# CardV1-ASCII.net
KiCad netlist of a schematic drawn in Altium Designer
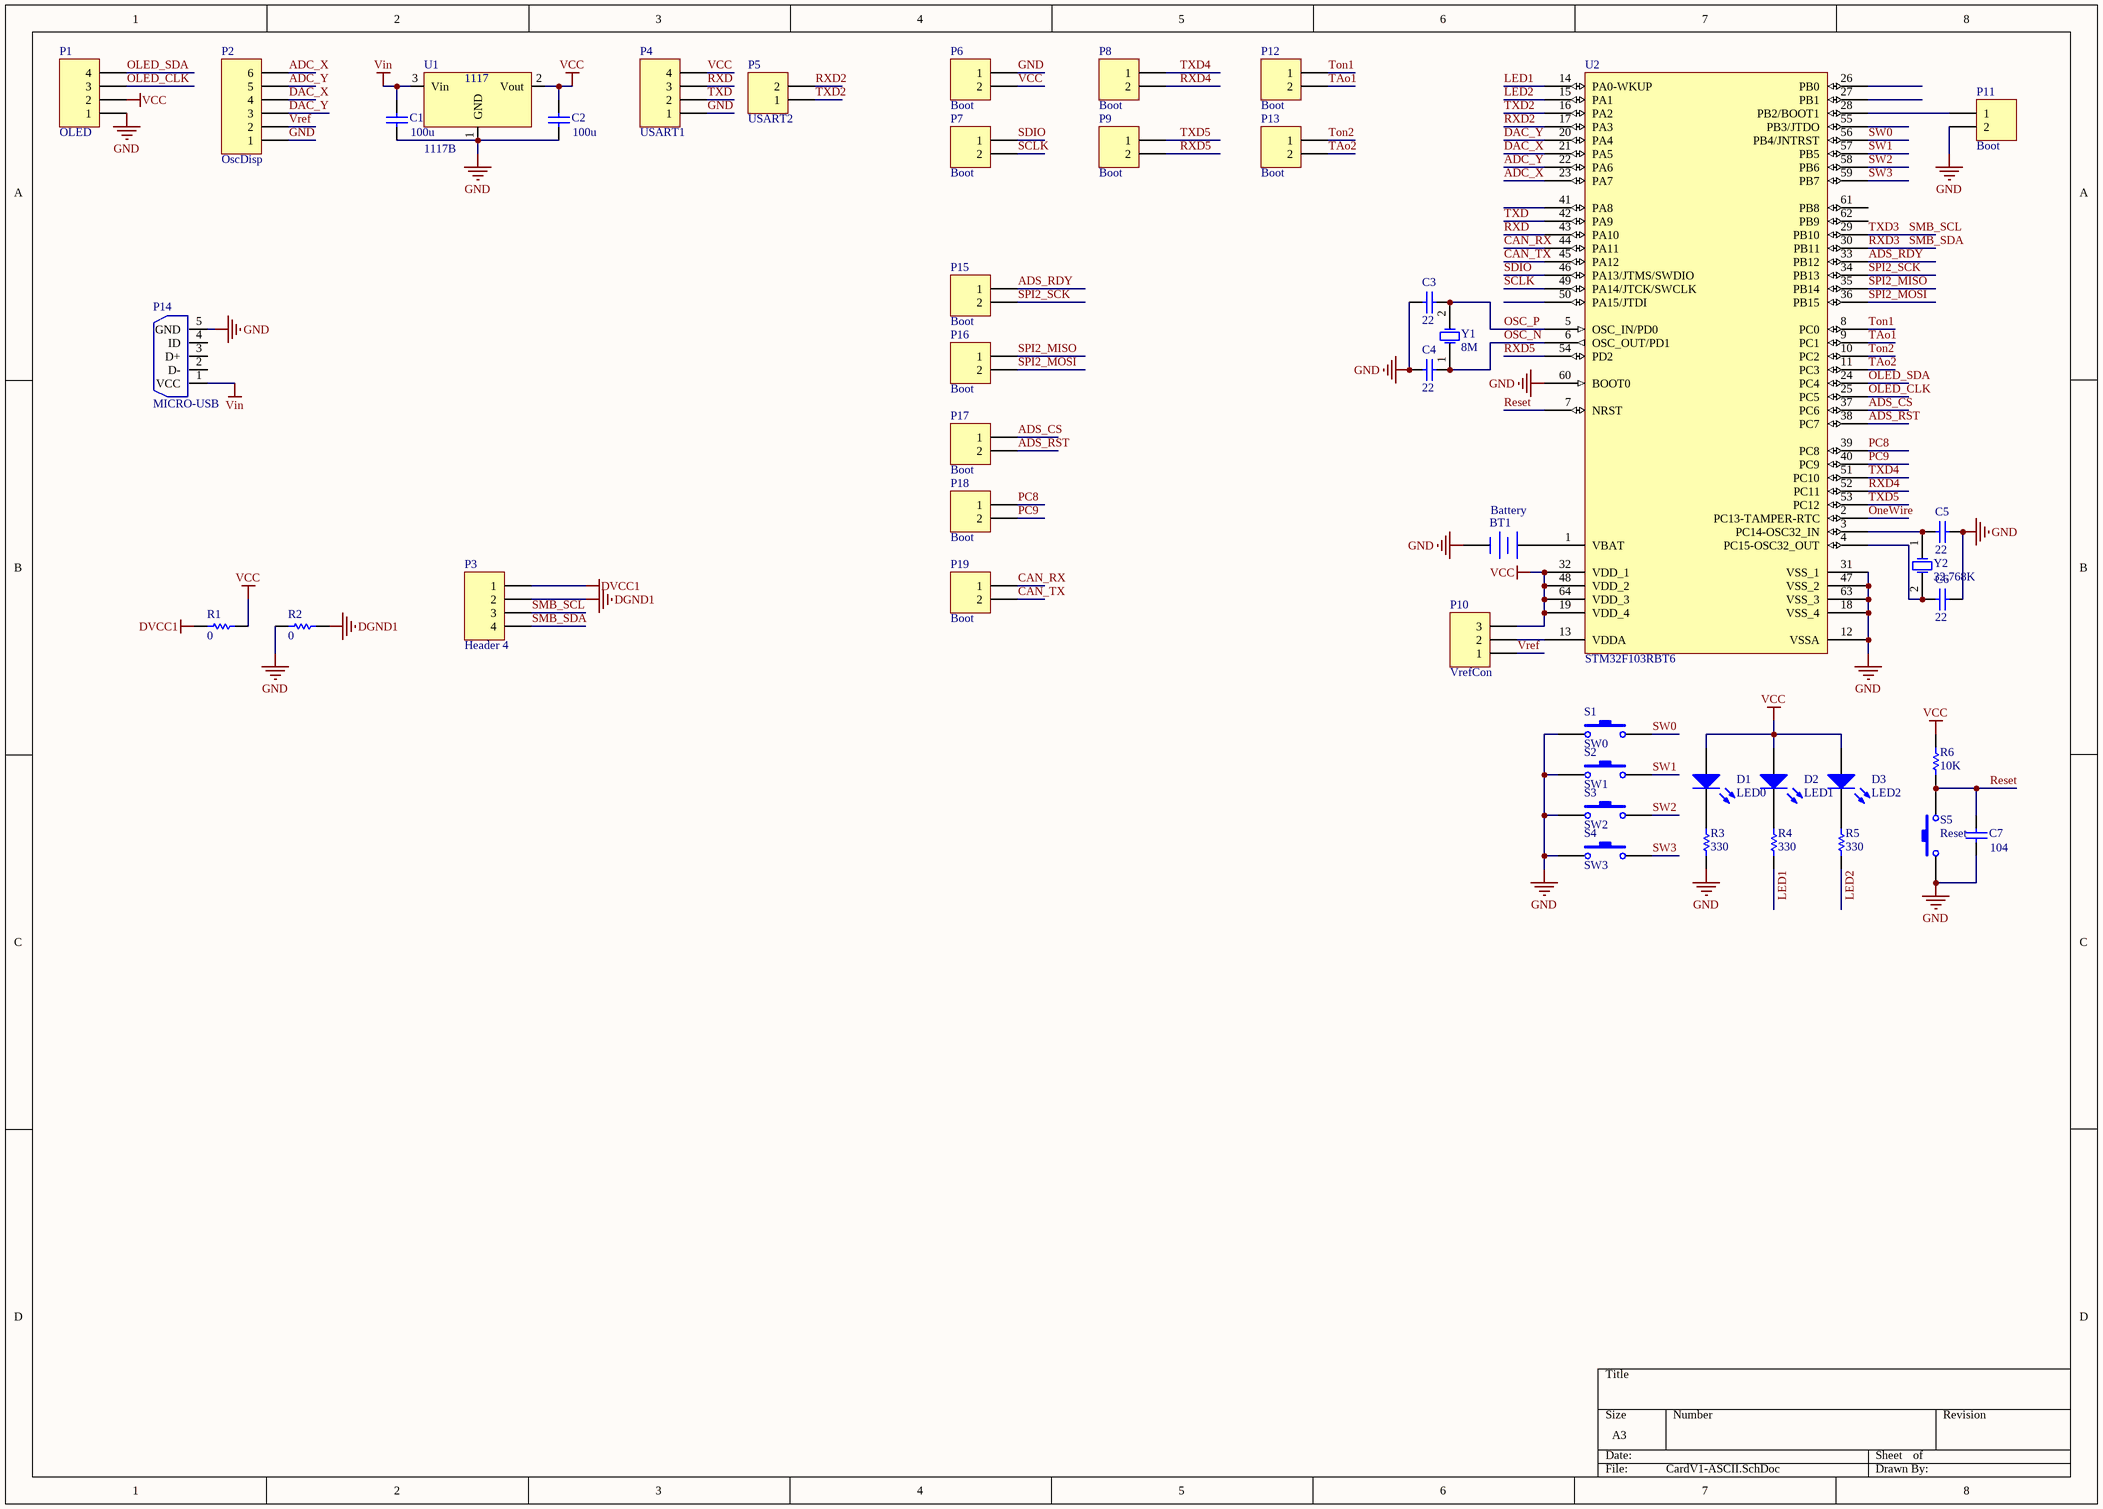
[diagram p0: CardV1-ASCII.SchDoc]

(export (version "E")
  (design (tool "Eeschema 10.0.6"))
  (components
    (comp (ref "BT1")
      (value "Battery")
      (footprint "Battery-OneSide")
      (description "Multicell Battery")
      (fields (field (name "PUBLISHER") "Altium Limited"))
      (libsource (lib "Miscellaneous Devices") (part "Battery"))
    )
    (comp (ref "C1")
      (value "100u")
      (footprint "1608[0603]")
      (description "Capacitor")
      (fields (field (name "PUBLISHER") "Altium Limited"))
      (libsource (lib "Miscellaneous Devices") (part "Cap"))
    )
    (comp (ref "C2")
      (value "100u")
      (footprint "1608[0603]")
      (description "Capacitor")
      (fields (field (name "PUBLISHER") "Altium Limited"))
      (libsource (lib "Miscellaneous Devices") (part "Cap"))
    )
    (comp (ref "C3")
      (value "22")
      (footprint "1608[0603]")
      (description "Capacitor")
      (fields (field (name "PUBLISHER") "Altium Limited"))
      (libsource (lib "Miscellaneous Devices") (part "Cap"))
    )
    (comp (ref "C4")
      (value "22")
      (footprint "1608[0603]")
      (description "Capacitor")
      (fields (field (name "PUBLISHER") "Altium Limited"))
      (libsource (lib "Miscellaneous Devices") (part "Cap"))
    )
    (comp (ref "C5")
      (value "22")
      (footprint "1608[0603]")
      (description "Capacitor")
      (fields (field (name "PUBLISHER") "Altium Limited"))
      (libsource (lib "Miscellaneous Devices") (part "Cap"))
    )
    (comp (ref "C6")
      (value "22")
      (footprint "1608[0603]")
      (description "Capacitor")
      (fields (field (name "PUBLISHER") "Altium Limited"))
      (libsource (lib "Miscellaneous Devices") (part "Cap"))
    )
    (comp (ref "C7")
      (value "104")
      (footprint "3.2X1.6X1.1")
      (description "Capacitor")
      (fields (field (name "PUBLISHER") "Altium Limited"))
      (libsource (lib "Miscellaneous Devices") (part "Cap"))
    )
    (comp (ref "D1")
      (value "LED0")
      (footprint "SMDLED")
      (description "Typical INFRARED GaAs LED")
      (fields (field (name "PUBLISHER") "Altium Limited"))
      (libsource (lib "Miscellaneous Devices") (part "LED0"))
    )
    (comp (ref "D2")
      (value "LED1")
      (footprint "SMDLED")
      (description "Typical INFRARED GaAs LED")
      (fields (field (name "PUBLISHER") "Altium Limited"))
      (libsource (lib "Miscellaneous Devices") (part "LED0"))
    )
    (comp (ref "D3")
      (value "LED2")
      (footprint "SMDLED")
      (description "Typical INFRARED GaAs LED")
      (fields (field (name "PUBLISHER") "Altium Limited"))
      (libsource (lib "Miscellaneous Devices") (part "LED0"))
    )
    (comp (ref "P1")
      (value "OLED")
      (footprint "HDR1X4")
      (description "Header, 4-Pin")
      (fields (field (name "PUBLISHER") "Altium Limited"))
      (libsource (lib "Miscellaneous Connectors") (part "Header 4"))
    )
    (comp (ref "P2")
      (value "OscDisp")
      (footprint "Postage6")
      (description "Header, 6-Pin")
      (fields (field (name "PUBLISHER") "Altium Limited"))
      (libsource (lib "Miscellaneous Connectors") (part "Header 6"))
    )
    (comp (ref "P3")
      (value "Header 4")
      (footprint "HDR1X4")
      (description "Header, 4-Pin")
      (fields (field (name "PUBLISHER") "Altium Limited"))
      (libsource (lib "") (part "Header 4_1"))
    )
    (comp (ref "P4")
      (value "USART1")
      (footprint "Postage4")
      (description "Header, 4-Pin")
      (fields (field (name "PUBLISHER") "Altium Limited"))
      (libsource (lib "Miscellaneous Connectors") (part "Header 4"))
    )
    (comp (ref "P5")
      (value "USART2")
      (footprint "Postage2")
      (description "Header, 2-Pin")
      (fields (field (name "PUBLISHER") "Altium Limited"))
      (libsource (lib "") (part "Header 2_1"))
    )
    (comp (ref "P6")
      (value "Boot")
      (footprint "Switch2")
      (description "Header, 2-Pin")
      (fields (field (name "PUBLISHER") "Altium Limited"))
      (libsource (lib "Miscellaneous Connectors") (part "Header 2"))
    )
    (comp (ref "P7")
      (value "Boot")
      (footprint "Switch2")
      (description "Header, 2-Pin")
      (fields (field (name "PUBLISHER") "Altium Limited"))
      (libsource (lib "Miscellaneous Connectors") (part "Header 2"))
    )
    (comp (ref "P8")
      (value "Boot")
      (footprint "Switch2")
      (description "Header, 2-Pin")
      (fields (field (name "PUBLISHER") "Altium Limited"))
      (libsource (lib "Miscellaneous Connectors") (part "Header 2"))
    )
    (comp (ref "P9")
      (value "Boot")
      (footprint "Switch2")
      (description "Header, 2-Pin")
      (fields (field (name "PUBLISHER") "Altium Limited"))
      (libsource (lib "Miscellaneous Connectors") (part "Header 2"))
    )
    (comp (ref "P10")
      (value "VrefCon")
      (footprint "Switch3")
      (description "Header, 3-Pin")
      (fields (field (name "PUBLISHER") "Altium Limited"))
      (libsource (lib "Miscellaneous Connectors") (part "Header 3"))
    )
    (comp (ref "P11")
      (value "Boot")
      (footprint "Switch2")
      (description "Header, 2-Pin")
      (fields (field (name "PUBLISHER") "Altium Limited"))
      (libsource (lib "") (part "Header 2_2"))
    )
    (comp (ref "P12")
      (value "Boot")
      (footprint "Switch2")
      (description "Header, 2-Pin")
      (fields (field (name "PUBLISHER") "Altium Limited"))
      (libsource (lib "Miscellaneous Connectors") (part "Header 2"))
    )
    (comp (ref "P13")
      (value "Boot")
      (footprint "Switch2")
      (description "Header, 2-Pin")
      (fields (field (name "PUBLISHER") "Altium Limited"))
      (libsource (lib "Miscellaneous Connectors") (part "Header 2"))
    )
    (comp (ref "P14")
      (value "MICRO-USB")
      (footprint "MICRO_USB5P_SOP")
      (libsource (lib "MiniFly ") (part "USB5"))
    )
    (comp (ref "P15")
      (value "Boot")
      (footprint "Switch2")
      (description "Header, 2-Pin")
      (fields (field (name "PUBLISHER") "Altium Limited"))
      (libsource (lib "Miscellaneous Connectors") (part "Header 2"))
    )
    (comp (ref "P16")
      (value "Boot")
      (footprint "Switch2")
      (description "Header, 2-Pin")
      (fields (field (name "PUBLISHER") "Altium Limited"))
      (libsource (lib "Miscellaneous Connectors") (part "Header 2"))
    )
    (comp (ref "P17")
      (value "Boot")
      (footprint "Switch2")
      (description "Header, 2-Pin")
      (fields (field (name "PUBLISHER") "Altium Limited"))
      (libsource (lib "Miscellaneous Connectors") (part "Header 2"))
    )
    (comp (ref "P18")
      (value "Boot")
      (footprint "Switch2")
      (description "Header, 2-Pin")
      (fields (field (name "PUBLISHER") "Altium Limited"))
      (libsource (lib "Miscellaneous Connectors") (part "Header 2"))
    )
    (comp (ref "P19")
      (value "Boot")
      (footprint "Switch2")
      (description "Header, 2-Pin")
      (fields (field (name "PUBLISHER") "Altium Limited"))
      (libsource (lib "Miscellaneous Connectors") (part "Header 2"))
    )
    (comp (ref "R1")
      (value "0")
      (footprint "0603P")
      (description "Resistor")
      (fields (field (name "PUBLISHER") "Altium Limited"))
      (libsource (lib "Miscellaneous Devices") (part "Res1"))
    )
    (comp (ref "R2")
      (value "0")
      (footprint "0603P")
      (description "Resistor")
      (fields (field (name "PUBLISHER") "Altium Limited"))
      (libsource (lib "Miscellaneous Devices") (part "Res1"))
    )
    (comp (ref "R3")
      (value "330")
      (footprint "0603P")
      (description "Resistor")
      (fields (field (name "PUBLISHER") "Altium Limited"))
      (libsource (lib "Miscellaneous Devices") (part "Res1"))
    )
    (comp (ref "R4")
      (value "330")
      (footprint "0603P")
      (description "Resistor")
      (fields (field (name "PUBLISHER") "Altium Limited"))
      (libsource (lib "Miscellaneous Devices") (part "Res1"))
    )
    (comp (ref "R5")
      (value "330")
      (footprint "0603P")
      (description "Resistor")
      (fields (field (name "PUBLISHER") "Altium Limited"))
      (libsource (lib "Miscellaneous Devices") (part "Res1"))
    )
    (comp (ref "R6")
      (value "10K")
      (footprint "0603P")
      (description "Resistor")
      (fields (field (name "PUBLISHER") "Altium Limited"))
      (libsource (lib "Miscellaneous Devices") (part "Res1"))
    )
    (comp (ref "S1")
      (value "SW0")
      (footprint "Key")
      (description "Switch")
      (fields (field (name "PUBLISHER") "Altium Limited"))
      (libsource (lib "Miscellaneous Devices") (part "SW-PB"))
    )
    (comp (ref "S2")
      (value "SW1")
      (footprint "Key")
      (description "Switch")
      (fields (field (name "PUBLISHER") "Altium Limited"))
      (libsource (lib "Miscellaneous Devices") (part "SW-PB"))
    )
    (comp (ref "S3")
      (value "SW2")
      (footprint "Key")
      (description "Switch")
      (fields (field (name "PUBLISHER") "Altium Limited"))
      (libsource (lib "Miscellaneous Devices") (part "SW-PB"))
    )
    (comp (ref "S4")
      (value "SW3")
      (footprint "Key")
      (description "Switch")
      (fields (field (name "PUBLISHER") "Altium Limited"))
      (libsource (lib "Miscellaneous Devices") (part "SW-PB"))
    )
    (comp (ref "S5")
      (value "Reset")
      (footprint "Key")
      (description "Switch")
      (fields (field (name "PUBLISHER") "Altium Limited"))
      (libsource (lib "Miscellaneous Devices") (part "SW-PB"))
    )
    (comp (ref "U1") (value "1117B") (footprint "SOP-223") (libsource (lib "MISCESCH") (part "1117B")))
    (comp (ref "U2")
      (value "STM32F103RBT6")
      (footprint "LQFP64_N")
      (description "STM32 ARM-based 32-bit MCU with 128 Kbytes Flash, 64-pin LQFP, Industrial Temperature")
      (fields (field (name "PUBLISHER") "Altium Limited"))
      (libsource (lib "ST Microcontroller 32-Bit STM32") (part "STM32F103RBT6"))
    )
    (comp (ref "Y1")
      (value "8M")
      (footprint "R38")
      (description "Crystal Oscillator")
      (fields (field (name "PUBLISHER") "Altium Limited"))
      (libsource (lib "Miscellaneous Devices") (part "XTAL"))
    )
    (comp (ref "Y2")
      (value "32.768K")
      (footprint "R38")
      (description "Crystal Oscillator")
      (fields (field (name "PUBLISHER") "Altium Limited"))
      (libsource (lib "Miscellaneous Devices") (part "XTAL"))
    )
  )
  (nets
    (net (code "1") (name "/ADC_X") (class "Default")
      (node (ref "P2") (pin "6") (pinfunction "6_6") (pintype "passive"))
      (node (ref "U2") (pin "23") (pinfunction "PA7_23") (pintype "bidirectional"))
    )
    (net (code "2") (name "/ADC_Y") (class "Default")
      (node (ref "P2") (pin "5") (pinfunction "5_5") (pintype "passive"))
      (node (ref "U2") (pin "22") (pinfunction "PA6_22") (pintype "bidirectional"))
    )
    (net (code "3") (name "/ADS_CS") (class "Default")
      (node (ref "P17") (pin "1") (pinfunction "1_1") (pintype "passive"))
      (node (ref "U2") (pin "37") (pinfunction "PC6_37") (pintype "bidirectional"))
    )
    (net (code "4") (name "/ADS_RDY") (class "Default")
      (node (ref "P15") (pin "1") (pinfunction "1_1") (pintype "passive"))
      (node (ref "U2") (pin "33") (pinfunction "PB12_33") (pintype "bidirectional"))
    )
    (net (code "5") (name "/ADS_RST") (class "Default")
      (node (ref "P17") (pin "2") (pinfunction "2_2") (pintype "passive"))
      (node (ref "U2") (pin "38") (pinfunction "PC7_38") (pintype "bidirectional"))
    )
    (net (code "6") (name "/CAN_RX") (class "Default")
      (node (ref "P19") (pin "1") (pinfunction "1_1") (pintype "passive"))
      (node (ref "U2") (pin "44") (pinfunction "PA11_44") (pintype "bidirectional"))
    )
    (net (code "7") (name "/CAN_TX") (class "Default")
      (node (ref "P19") (pin "2") (pinfunction "2_2") (pintype "passive"))
      (node (ref "U2") (pin "45") (pinfunction "PA12_45") (pintype "bidirectional"))
    )
    (net (code "8") (name "/DAC_X") (class "Default")
      (node (ref "P2") (pin "4") (pinfunction "4_4") (pintype "passive"))
      (node (ref "U2") (pin "21") (pinfunction "PA5_21") (pintype "bidirectional"))
    )
    (net (code "9") (name "/DAC_Y") (class "Default")
      (node (ref "P2") (pin "3") (pinfunction "3_3") (pintype "passive"))
      (node (ref "U2") (pin "20") (pinfunction "PA4_20") (pintype "bidirectional"))
    )
    (net (code "10") (name "/LED1") (class "Default")
      (node (ref "R4") (pin "1") (pinfunction "1_1") (pintype "passive"))
      (node (ref "U2") (pin "14") (pinfunction "PA0-WKUP_14") (pintype "bidirectional"))
    )
    (net (code "11") (name "/LED2") (class "Default")
      (node (ref "R5") (pin "1") (pinfunction "1_1") (pintype "passive"))
      (node (ref "U2") (pin "15") (pinfunction "PA1_15") (pintype "bidirectional"))
    )
    (net (code "12") (name "/OLED_CLK") (class "Default")
      (node (ref "P1") (pin "3") (pinfunction "3_3") (pintype "passive"))
      (node (ref "U2") (pin "25") (pinfunction "PC5_25") (pintype "bidirectional"))
    )
    (net (code "13") (name "/OLED_SDA") (class "Default")
      (node (ref "P1") (pin "4") (pinfunction "4_4") (pintype "passive"))
      (node (ref "U2") (pin "24") (pinfunction "PC4_24") (pintype "bidirectional"))
    )
    (net (code "14") (name "/OSC_N") (class "Default")
      (node (ref "C4") (pin "2") (pinfunction "2_2") (pintype "passive"))
      (node (ref "U2") (pin "6") (pinfunction "OSC_OUT/PD1_6") (pintype "output"))
      (node (ref "Y1") (pin "1") (pinfunction "OSC1_1") (pintype "passive"))
    )
    (net (code "15") (name "/OSC_P") (class "Default")
      (node (ref "C3") (pin "1") (pinfunction "1_1") (pintype "passive"))
      (node (ref "U2") (pin "5") (pinfunction "OSC_IN/PD0_5") (pintype "input"))
      (node (ref "Y1") (pin "2") (pinfunction "OSC2_2") (pintype "passive"))
    )
    (net (code "16") (name "/OneWire") (class "Default")
      (node (ref "U2") (pin "2") (pinfunction "PC13-TAMPER-RTC_2") (pintype "bidirectional"))
    )
    (net (code "17") (name "/PC8") (class "Default")
      (node (ref "P18") (pin "1") (pinfunction "1_1") (pintype "passive"))
      (node (ref "U2") (pin "39") (pinfunction "PC8_39") (pintype "bidirectional"))
    )
    (net (code "18") (name "/PC9") (class "Default")
      (node (ref "P18") (pin "2") (pinfunction "2_2") (pintype "passive"))
      (node (ref "U2") (pin "40") (pinfunction "PC9_40") (pintype "bidirectional"))
    )
    (net (code "19") (name "/RXD") (class "Default")
      (node (ref "P4") (pin "3") (pinfunction "3_3") (pintype "passive"))
      (node (ref "U2") (pin "43") (pinfunction "PA10_43") (pintype "bidirectional"))
    )
    (net (code "20") (name "/RXD2") (class "Default")
      (node (ref "P5") (pin "2") (pinfunction "2_2") (pintype "passive"))
      (node (ref "U2") (pin "17") (pinfunction "PA3_17") (pintype "bidirectional"))
    )
    (net (code "21") (name "/RXD3") (class "Default")
      (node (ref "P3") (pin "4") (pinfunction "4_4") (pintype "passive"))
      (node (ref "U2") (pin "30") (pinfunction "PB11_30") (pintype "bidirectional"))
    )
    (net (code "22") (name "/RXD4") (class "Default")
      (node (ref "P8") (pin "2") (pinfunction "2_2") (pintype "passive"))
      (node (ref "U2") (pin "52") (pinfunction "PC11_52") (pintype "bidirectional"))
    )
    (net (code "23") (name "/RXD5") (class "Default")
      (node (ref "P9") (pin "2") (pinfunction "2_2") (pintype "passive"))
      (node (ref "U2") (pin "54") (pinfunction "PD2_54") (pintype "bidirectional"))
    )
    (net (code "24") (name "/Reset") (class "Default")
      (node (ref "C7") (pin "2") (pinfunction "2_2") (pintype "passive"))
      (node (ref "R6") (pin "1") (pinfunction "1_1") (pintype "passive"))
      (node (ref "S5") (pin "2") (pinfunction "2_2") (pintype "passive"))
      (node (ref "U2") (pin "7") (pinfunction "NRST_7") (pintype "bidirectional"))
    )
    (net (code "25") (name "/SCLK") (class "Default")
      (node (ref "P7") (pin "2") (pinfunction "2_2") (pintype "passive"))
      (node (ref "U2") (pin "49") (pinfunction "PA14/JTCK/SWCLK_49") (pintype "bidirectional"))
    )
    (net (code "26") (name "/SDIO") (class "Default")
      (node (ref "P7") (pin "1") (pinfunction "1_1") (pintype "passive"))
      (node (ref "U2") (pin "46") (pinfunction "PA13/JTMS/SWDIO_46") (pintype "bidirectional"))
    )
    (net (code "27") (name "/SMB_SCL") (class "Default")
      (node (ref "P3") (pin "3") (pinfunction "3_3") (pintype "passive"))
      (node (ref "U2") (pin "29") (pinfunction "PB10_29") (pintype "bidirectional"))
    )
    (net (code "28") (name "/SPI2_MISO") (class "Default")
      (node (ref "P16") (pin "1") (pinfunction "1_1") (pintype "passive"))
      (node (ref "U2") (pin "35") (pinfunction "PB14_35") (pintype "bidirectional"))
    )
    (net (code "29") (name "/SPI2_MOSI") (class "Default")
      (node (ref "P16") (pin "2") (pinfunction "2_2") (pintype "passive"))
      (node (ref "U2") (pin "36") (pinfunction "PB15_36") (pintype "bidirectional"))
    )
    (net (code "30") (name "/SPI2_SCK") (class "Default")
      (node (ref "P15") (pin "2") (pinfunction "2_2") (pintype "passive"))
      (node (ref "U2") (pin "34") (pinfunction "PB13_34") (pintype "bidirectional"))
    )
    (net (code "31") (name "/SW0") (class "Default")
      (node (ref "S1") (pin "2") (pinfunction "2_2") (pintype "passive"))
      (node (ref "U2") (pin "56") (pinfunction "PB4/JNTRST_56") (pintype "bidirectional"))
    )
    (net (code "32") (name "/SW1") (class "Default")
      (node (ref "S2") (pin "2") (pinfunction "2_2") (pintype "passive"))
      (node (ref "U2") (pin "57") (pinfunction "PB5_57") (pintype "bidirectional"))
    )
    (net (code "33") (name "/SW2") (class "Default")
      (node (ref "S3") (pin "2") (pinfunction "2_2") (pintype "passive"))
      (node (ref "U2") (pin "58") (pinfunction "PB6_58") (pintype "bidirectional"))
    )
    (net (code "34") (name "/SW3") (class "Default")
      (node (ref "S4") (pin "2") (pinfunction "2_2") (pintype "passive"))
      (node (ref "U2") (pin "59") (pinfunction "PB7_59") (pintype "bidirectional"))
    )
    (net (code "35") (name "/TAo1") (class "Default")
      (node (ref "P12") (pin "2") (pinfunction "2_2") (pintype "passive"))
      (node (ref "U2") (pin "9") (pinfunction "PC1_9") (pintype "bidirectional"))
    )
    (net (code "36") (name "/TAo2") (class "Default")
      (node (ref "P13") (pin "2") (pinfunction "2_2") (pintype "passive"))
      (node (ref "U2") (pin "11") (pinfunction "PC3_11") (pintype "bidirectional"))
    )
    (net (code "37") (name "/TXD") (class "Default")
      (node (ref "P4") (pin "2") (pinfunction "2_2") (pintype "passive"))
      (node (ref "U2") (pin "42") (pinfunction "PA9_42") (pintype "bidirectional"))
    )
    (net (code "38") (name "/TXD2") (class "Default")
      (node (ref "P5") (pin "1") (pinfunction "1_1") (pintype "passive"))
      (node (ref "U2") (pin "16") (pinfunction "PA2_16") (pintype "bidirectional"))
    )
    (net (code "39") (name "/TXD4") (class "Default")
      (node (ref "P8") (pin "1") (pinfunction "1_1") (pintype "passive"))
      (node (ref "U2") (pin "51") (pinfunction "PC10_51") (pintype "bidirectional"))
    )
    (net (code "40") (name "/TXD5") (class "Default")
      (node (ref "P9") (pin "1") (pinfunction "1_1") (pintype "passive"))
      (node (ref "U2") (pin "53") (pinfunction "PC12_53") (pintype "bidirectional"))
    )
    (net (code "41") (name "/Ton1") (class "Default")
      (node (ref "P12") (pin "1") (pinfunction "1_1") (pintype "passive"))
      (node (ref "U2") (pin "8") (pinfunction "PC0_8") (pintype "bidirectional"))
    )
    (net (code "42") (name "/Ton2") (class "Default")
      (node (ref "P13") (pin "1") (pinfunction "1_1") (pintype "passive"))
      (node (ref "U2") (pin "10") (pinfunction "PC2_10") (pintype "bidirectional"))
    )
    (net (code "43") (name "/Vref") (class "Default")
      (node (ref "P10") (pin "1") (pinfunction "1_1") (pintype "passive"))
      (node (ref "P2") (pin "2") (pinfunction "2_2") (pintype "passive"))
    )
    (net (code "44") (name "DGND1") (class "Default")
      (node (ref "P3") (pin "2") (pinfunction "2_2") (pintype "passive"))
      (node (ref "R2") (pin "2") (pinfunction "2_2") (pintype "passive"))
    )
    (net (code "45") (name "DVCC1") (class "Default")
      (node (ref "P3") (pin "1") (pinfunction "1_1") (pintype "passive"))
      (node (ref "R1") (pin "2") (pinfunction "2_2") (pintype "passive"))
    )
    (net (code "46") (name "GND") (class "Default")
      (node (ref "BT1") (pin "2") (pinfunction "-_2") (pintype "passive"))
      (node (ref "C1") (pin "1") (pinfunction "1_1") (pintype "passive"))
      (node (ref "C2") (pin "1") (pinfunction "1_1") (pintype "passive"))
      (node (ref "C3") (pin "2") (pinfunction "2_2") (pintype "passive"))
      (node (ref "C4") (pin "1") (pinfunction "1_1") (pintype "passive"))
      (node (ref "C5") (pin "2") (pinfunction "2_2") (pintype "passive"))
      (node (ref "C6") (pin "2") (pinfunction "2_2") (pintype "passive"))
      (node (ref "C7") (pin "1") (pinfunction "1_1") (pintype "passive"))
      (node (ref "P1") (pin "1") (pinfunction "1_1") (pintype "passive"))
      (node (ref "P11") (pin "2") (pinfunction "2_2") (pintype "passive"))
      (node (ref "P14") (pin "5") (pinfunction "GND_5") (pintype "passive"))
      (node (ref "P2") (pin "1") (pinfunction "1_1") (pintype "passive"))
      (node (ref "P4") (pin "1") (pinfunction "1_1") (pintype "passive"))
      (node (ref "P6") (pin "1") (pinfunction "1_1") (pintype "passive"))
      (node (ref "R2") (pin "1") (pinfunction "1_1") (pintype "passive"))
      (node (ref "R3") (pin "2") (pinfunction "2_2") (pintype "passive"))
      (node (ref "S1") (pin "1") (pinfunction "1_1") (pintype "passive"))
      (node (ref "S2") (pin "1") (pinfunction "1_1") (pintype "passive"))
      (node (ref "S3") (pin "1") (pinfunction "1_1") (pintype "passive"))
      (node (ref "S4") (pin "1") (pinfunction "1_1") (pintype "passive"))
      (node (ref "S5") (pin "1") (pinfunction "1_1") (pintype "passive"))
      (node (ref "U1") (pin "1") (pinfunction "GND_1") (pintype "passive"))
      (node (ref "U2") (pin "12") (pinfunction "VSSA_12") (pintype "power_in"))
      (node (ref "U2") (pin "18") (pinfunction "VSS_4_18") (pintype "power_in"))
      (node (ref "U2") (pin "31") (pinfunction "VSS_1_31") (pintype "power_in"))
      (node (ref "U2") (pin "47") (pinfunction "VSS_2_47") (pintype "power_in"))
      (node (ref "U2") (pin "60") (pinfunction "BOOT0_60") (pintype "input"))
      (node (ref "U2") (pin "63") (pinfunction "VSS_3_63") (pintype "power_in"))
    )
    (net (code "47") (name "Net-(BT1-+)") (class "Default")
      (node (ref "BT1") (pin "1") (pinfunction "+_1") (pintype "passive"))
      (node (ref "U2") (pin "1") (pinfunction "VBAT_1") (pintype "power_in"))
    )
    (net (code "48") (name "Net-(D1-K)") (class "Default")
      (node (ref "D1") (pin "2") (pinfunction "K_2") (pintype "passive"))
      (node (ref "R3") (pin "1") (pinfunction "1_1") (pintype "passive"))
    )
    (net (code "49") (name "Net-(D2-K)") (class "Default")
      (node (ref "D2") (pin "2") (pinfunction "K_2") (pintype "passive"))
      (node (ref "R4") (pin "2") (pinfunction "2_2") (pintype "passive"))
    )
    (net (code "50") (name "Net-(D3-K)") (class "Default")
      (node (ref "D3") (pin "2") (pinfunction "K_2") (pintype "passive"))
      (node (ref "R5") (pin "2") (pinfunction "2_2") (pintype "passive"))
    )
    (net (code "51") (name "Net-(U2-PB2{slash}BOOT1)") (class "Default")
      (node (ref "P11") (pin "1") (pinfunction "1_1") (pintype "passive"))
      (node (ref "U2") (pin "28") (pinfunction "PB2/BOOT1_28") (pintype "bidirectional"))
    )
    (net (code "52") (name "Net-(U2-PC14-OSC32_IN)") (class "Default")
      (node (ref "C5") (pin "1") (pinfunction "1_1") (pintype "passive"))
      (node (ref "U2") (pin "3") (pinfunction "PC14-OSC32_IN_3") (pintype "bidirectional"))
      (node (ref "Y2") (pin "1") (pinfunction "OSC1_1") (pintype "passive"))
    )
    (net (code "53") (name "Net-(U2-PC15-OSC32_OUT)") (class "Default")
      (node (ref "C6") (pin "1") (pinfunction "1_1") (pintype "passive"))
      (node (ref "U2") (pin "4") (pinfunction "PC15-OSC32_OUT_4") (pintype "bidirectional"))
      (node (ref "Y2") (pin "2") (pinfunction "OSC2_2") (pintype "passive"))
    )
    (net (code "54") (name "Net-(U2-VDDA)") (class "Default")
      (node (ref "P10") (pin "2") (pinfunction "2_2") (pintype "passive"))
      (node (ref "U2") (pin "13") (pinfunction "VDDA_13") (pintype "power_in"))
    )
    (net (code "55") (name "VCC") (class "Default")
      (node (ref "C2") (pin "2") (pinfunction "2_2") (pintype "passive"))
      (node (ref "D1") (pin "1") (pinfunction "A_1") (pintype "passive"))
      (node (ref "D2") (pin "1") (pinfunction "A_1") (pintype "passive"))
      (node (ref "D3") (pin "1") (pinfunction "A_1") (pintype "passive"))
      (node (ref "P1") (pin "2") (pinfunction "2_2") (pintype "passive"))
      (node (ref "P10") (pin "3") (pinfunction "3_3") (pintype "passive"))
      (node (ref "P4") (pin "4") (pinfunction "4_4") (pintype "passive"))
      (node (ref "P6") (pin "2") (pinfunction "2_2") (pintype "passive"))
      (node (ref "R1") (pin "1") (pinfunction "1_1") (pintype "passive"))
      (node (ref "R6") (pin "2") (pinfunction "2_2") (pintype "passive"))
      (node (ref "U1") (pin "2") (pinfunction "Vout_2") (pintype "passive"))
      (node (ref "U2") (pin "19") (pinfunction "VDD_4_19") (pintype "power_in"))
      (node (ref "U2") (pin "32") (pinfunction "VDD_1_32") (pintype "power_in"))
      (node (ref "U2") (pin "48") (pinfunction "VDD_2_48") (pintype "power_in"))
      (node (ref "U2") (pin "64") (pinfunction "VDD_3_64") (pintype "power_in"))
    )
    (net (code "56") (name "Vin") (class "Default")
      (node (ref "C1") (pin "2") (pinfunction "2_2") (pintype "passive"))
      (node (ref "P14") (pin "1") (pinfunction "VCC_1") (pintype "passive"))
      (node (ref "U1") (pin "3") (pinfunction "Vin_3") (pintype "passive"))
    )
    (net (code "57") (name "unconnected-(P14-D+-Pad3)") (class "Default")
      (node (ref "P14") (pin "3") (pinfunction "D+_3") (pintype "passive"))
    )
    (net (code "58") (name "unconnected-(P14-D--Pad2)") (class "Default")
      (node (ref "P14") (pin "2") (pinfunction "D-_2") (pintype "passive"))
    )
    (net (code "59") (name "unconnected-(P14-ID-Pad4)") (class "Default")
      (node (ref "P14") (pin "4") (pinfunction "ID_4") (pintype "passive"))
    )
    (net (code "60") (name "unconnected-(U2-PA8-Pad41)") (class "Default")
      (node (ref "U2") (pin "41") (pinfunction "PA8_41") (pintype "bidirectional"))
    )
    (net (code "61") (name "unconnected-(U2-PA15{slash}JTDI-Pad50)") (class "Default")
      (node (ref "U2") (pin "50") (pinfunction "PA15/JTDI_50") (pintype "bidirectional"))
    )
    (net (code "62") (name "unconnected-(U2-PB0-Pad26)") (class "Default")
      (node (ref "U2") (pin "26") (pinfunction "PB0_26") (pintype "bidirectional"))
    )
    (net (code "63") (name "unconnected-(U2-PB1-Pad27)") (class "Default")
      (node (ref "U2") (pin "27") (pinfunction "PB1_27") (pintype "bidirectional"))
    )
    (net (code "64") (name "unconnected-(U2-PB3{slash}JTDO-Pad55)") (class "Default")
      (node (ref "U2") (pin "55") (pinfunction "PB3/JTDO_55") (pintype "bidirectional"))
    )
    (net (code "65") (name "unconnected-(U2-PB8-Pad61)") (class "Default")
      (node (ref "U2") (pin "61") (pinfunction "PB8_61") (pintype "bidirectional"))
    )
    (net (code "66") (name "unconnected-(U2-PB9-Pad62)") (class "Default")
      (node (ref "U2") (pin "62") (pinfunction "PB9_62") (pintype "bidirectional"))
    )
  )
)
